# LlenadoPiscina.net
KiCad netlist of a schematic drawn in EAGLE
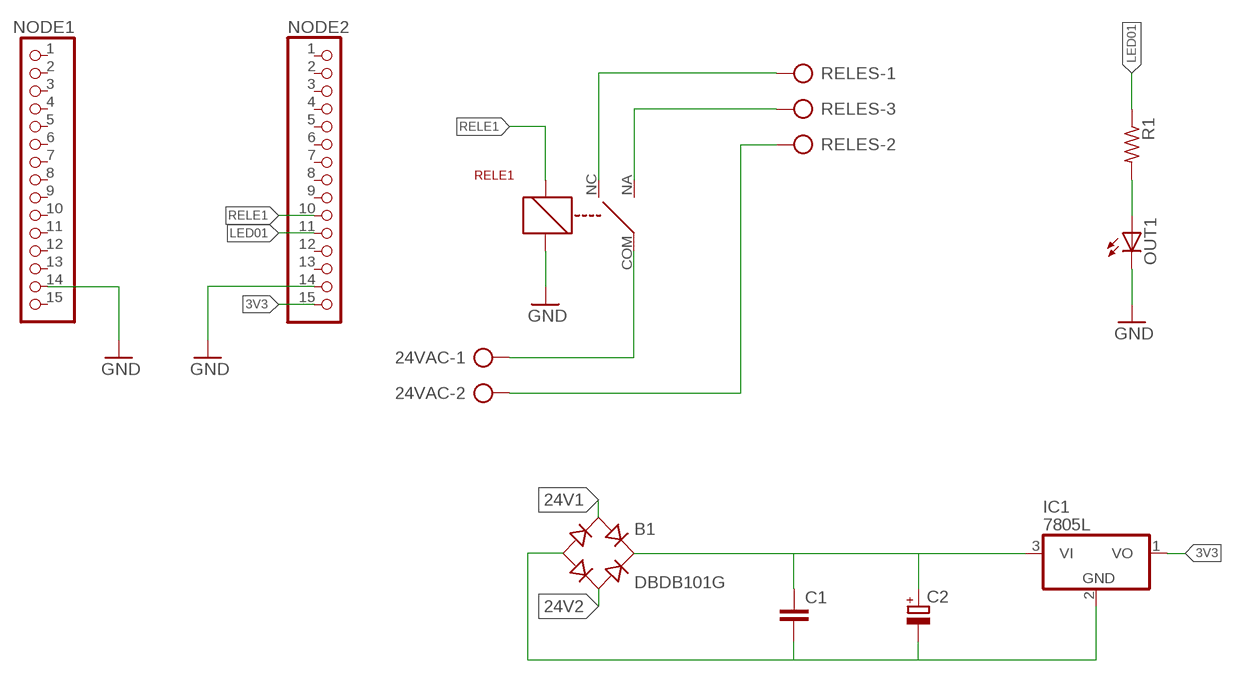
[diagram p0: schematic, sheet 1]

(export (version "E")
  (design (tool "Eeschema 10.0.6"))
  (components
    (comp (ref "24VAC")
      (value "AK500/2-H")
      (footprint "eagle-import:AK500_2-H")
      (libsource (lib "eagle-import") (part "AK500/2-H"))
    )
    (comp (ref "B1")
      (value "DBDB101G")
      (footprint "eagle-import:DB")
      (libsource (lib "eagle-import") (part "DB?GDB101"))
    )
    (comp (ref "C1")
      (value "C2.5/2")
      (footprint "eagle-import:C2.5-2")
      (libsource (lib "eagle-import") (part "C2.5/2"))
    )
    (comp (ref "C2")
      (value "CPOL-EUE2,5-6E")
      (footprint "eagle-import:E2,5-6E")
      (libsource (lib "eagle-import") (part "CPOL-EUE2,5-6E"))
    )
    (comp (ref "IC1")
      (value "7805L")
      (footprint "eagle-import:TO92")
      (libsource (lib "eagle-import") (part "78L05"))
    )
    (comp (ref "NODE1")
      (value "PINHD-1X15")
      (footprint "eagle-import:1X15")
      (libsource (lib "eagle-import") (part "PINHD-1X15"))
    )
    (comp (ref "NODE2")
      (value "PINHD-1X15")
      (footprint "eagle-import:1X15")
      (libsource (lib "eagle-import") (part "PINHD-1X15"))
    )
    (comp (ref "OUT1")
      (value "LED3MM")
      (footprint "eagle-import:LED3MM")
      (libsource (lib "eagle-import") (part "LED3MM"))
    )
    (comp (ref "R1")
      (value "R-US_0204/7")
      (footprint "eagle-import:0204_7")
      (libsource (lib "eagle-import") (part "R-US_0204/7"))
    )
    (comp (ref "RELE1")
      (value "RAS0510")
      (footprint "eagle-import:RAS0510")
      (libsource (lib "eagle-import") (part "RAS0510"))
    )
    (comp (ref "RELES")
      (value "AK500/3-H")
      (footprint "eagle-import:AK500_3-H")
      (libsource (lib "eagle-import") (part "AK500/3-H"))
    )
  )
  (nets
    (net (code "1") (name "3V3") (class "Default")
      (node (ref "IC1") (pin "1") (pinfunction "VO_1") (pintype "passive"))
      (node (ref "NODE2") (pin "15") (pinfunction "15_15") (pintype "passive"))
    )
    (net (code "2") (name "24V1") (class "Default")
      (node (ref "24VAC") (pin "1") (pinfunction "KL_1") (pintype "passive"))
      (node (ref "B1") (pin "AC1") (pinfunction "AC1_AC1") (pintype "passive"))
      (node (ref "RELE1") (pin "COM") (pinfunction "COM_COM") (pintype "bidirectional"))
    )
    (net (code "3") (name "24V2") (class "Default")
      (node (ref "24VAC") (pin "2") (pinfunction "KL_2") (pintype "passive"))
      (node (ref "B1") (pin "AC2") (pinfunction "AC2_AC2") (pintype "passive"))
      (node (ref "RELES") (pin "2") (pinfunction "KL_2") (pintype "passive"))
    )
    (net (code "4") (name "GND") (class "Default")
      (node (ref "NODE1") (pin "14") (pinfunction "14_14") (pintype "passive"))
      (node (ref "NODE2") (pin "14") (pinfunction "14_14") (pintype "passive"))
      (node (ref "OUT1") (pin "K") (pinfunction "C_K") (pintype "passive"))
      (node (ref "RELE1") (pin "B2") (pinfunction "B2_B2") (pintype "bidirectional"))
    )
    (net (code "5") (name "LED01") (class "Default")
      (node (ref "NODE2") (pin "11") (pinfunction "11_11") (pintype "passive"))
      (node (ref "R1") (pin "1") (pinfunction "1_1") (pintype "passive"))
    )
    (net (code "6") (name "Net-(IC1-GND)") (class "Default")
      (node (ref "B1") (pin "-") (pinfunction "-_-") (pintype "passive"))
      (node (ref "C1") (pin "2") (pinfunction "2_2") (pintype "passive"))
      (node (ref "C2") (pin "-") (pinfunction "-_-") (pintype "passive"))
      (node (ref "IC1") (pin "2") (pinfunction "GND_2") (pintype "passive"))
    )
    (net (code "7") (name "Net-(IC1-VI)") (class "Default")
      (node (ref "B1") (pin "+") (pinfunction "+_+") (pintype "passive"))
      (node (ref "C1") (pin "1") (pinfunction "1_1") (pintype "passive"))
      (node (ref "C2") (pin "+") (pinfunction "+_+") (pintype "passive"))
      (node (ref "IC1") (pin "3") (pinfunction "VI_3") (pintype "input"))
    )
    (net (code "8") (name "Net-(OUT1-PadA)") (class "Default")
      (node (ref "OUT1") (pin "A") (pinfunction "A_A") (pintype "passive"))
      (node (ref "R1") (pin "2") (pinfunction "2_2") (pintype "passive"))
    )
    (net (code "9") (name "Net-(RELESA-KL)") (class "Default")
      (node (ref "RELE1") (pin "NC") (pinfunction "NC_NC") (pintype "bidirectional"))
      (node (ref "RELES") (pin "1") (pinfunction "KL_1") (pintype "passive"))
    )
    (net (code "10") (name "Net-(RELESC-KL)") (class "Default")
      (node (ref "RELE1") (pin "NA") (pinfunction "NA_NA") (pintype "bidirectional"))
      (node (ref "RELES") (pin "3") (pinfunction "KL_3") (pintype "passive"))
    )
    (net (code "11") (name "RELE1") (class "Default")
      (node (ref "NODE2") (pin "10") (pinfunction "10_10") (pintype "passive"))
      (node (ref "RELE1") (pin "B1") (pinfunction "B1_B1") (pintype "bidirectional"))
    )
    (net (code "12") (name "unconnected-(NODE1-Pad1)") (class "Default")
      (node (ref "NODE1") (pin "1") (pinfunction "1_1") (pintype "passive"))
    )
    (net (code "13") (name "unconnected-(NODE1-Pad2)") (class "Default")
      (node (ref "NODE1") (pin "2") (pinfunction "2_2") (pintype "passive"))
    )
    (net (code "14") (name "unconnected-(NODE1-Pad3)") (class "Default")
      (node (ref "NODE1") (pin "3") (pinfunction "3_3") (pintype "passive"))
    )
    (net (code "15") (name "unconnected-(NODE1-Pad4)") (class "Default")
      (node (ref "NODE1") (pin "4") (pinfunction "4_4") (pintype "passive"))
    )
    (net (code "16") (name "unconnected-(NODE1-Pad5)") (class "Default")
      (node (ref "NODE1") (pin "5") (pinfunction "5_5") (pintype "passive"))
    )
    (net (code "17") (name "unconnected-(NODE1-Pad6)") (class "Default")
      (node (ref "NODE1") (pin "6") (pinfunction "6_6") (pintype "passive"))
    )
    (net (code "18") (name "unconnected-(NODE1-Pad7)") (class "Default")
      (node (ref "NODE1") (pin "7") (pinfunction "7_7") (pintype "passive"))
    )
    (net (code "19") (name "unconnected-(NODE1-Pad8)") (class "Default")
      (node (ref "NODE1") (pin "8") (pinfunction "8_8") (pintype "passive"))
    )
    (net (code "20") (name "unconnected-(NODE1-Pad9)") (class "Default")
      (node (ref "NODE1") (pin "9") (pinfunction "9_9") (pintype "passive"))
    )
    (net (code "21") (name "unconnected-(NODE1-Pad10)") (class "Default")
      (node (ref "NODE1") (pin "10") (pinfunction "10_10") (pintype "passive"))
    )
    (net (code "22") (name "unconnected-(NODE1-Pad11)") (class "Default")
      (node (ref "NODE1") (pin "11") (pinfunction "11_11") (pintype "passive"))
    )
    (net (code "23") (name "unconnected-(NODE1-Pad12)") (class "Default")
      (node (ref "NODE1") (pin "12") (pinfunction "12_12") (pintype "passive"))
    )
    (net (code "24") (name "unconnected-(NODE1-Pad13)") (class "Default")
      (node (ref "NODE1") (pin "13") (pinfunction "13_13") (pintype "passive"))
    )
    (net (code "25") (name "unconnected-(NODE1-Pad15)") (class "Default")
      (node (ref "NODE1") (pin "15") (pinfunction "15_15") (pintype "passive"))
    )
    (net (code "26") (name "unconnected-(NODE2-Pad1)") (class "Default")
      (node (ref "NODE2") (pin "1") (pinfunction "1_1") (pintype "passive"))
    )
    (net (code "27") (name "unconnected-(NODE2-Pad2)") (class "Default")
      (node (ref "NODE2") (pin "2") (pinfunction "2_2") (pintype "passive"))
    )
    (net (code "28") (name "unconnected-(NODE2-Pad3)") (class "Default")
      (node (ref "NODE2") (pin "3") (pinfunction "3_3") (pintype "passive"))
    )
    (net (code "29") (name "unconnected-(NODE2-Pad4)") (class "Default")
      (node (ref "NODE2") (pin "4") (pinfunction "4_4") (pintype "passive"))
    )
    (net (code "30") (name "unconnected-(NODE2-Pad5)") (class "Default")
      (node (ref "NODE2") (pin "5") (pinfunction "5_5") (pintype "passive"))
    )
    (net (code "31") (name "unconnected-(NODE2-Pad6)") (class "Default")
      (node (ref "NODE2") (pin "6") (pinfunction "6_6") (pintype "passive"))
    )
    (net (code "32") (name "unconnected-(NODE2-Pad7)") (class "Default")
      (node (ref "NODE2") (pin "7") (pinfunction "7_7") (pintype "passive"))
    )
    (net (code "33") (name "unconnected-(NODE2-Pad8)") (class "Default")
      (node (ref "NODE2") (pin "8") (pinfunction "8_8") (pintype "passive"))
    )
    (net (code "34") (name "unconnected-(NODE2-Pad9)") (class "Default")
      (node (ref "NODE2") (pin "9") (pinfunction "9_9") (pintype "passive"))
    )
    (net (code "35") (name "unconnected-(NODE2-Pad12)") (class "Default")
      (node (ref "NODE2") (pin "12") (pinfunction "12_12") (pintype "passive"))
    )
    (net (code "36") (name "unconnected-(NODE2-Pad13)") (class "Default")
      (node (ref "NODE2") (pin "13") (pinfunction "13_13") (pintype "passive"))
    )
  )
)
